# 36V_Supply.net
KiCad netlist of a schematic drawn in Altium Designer
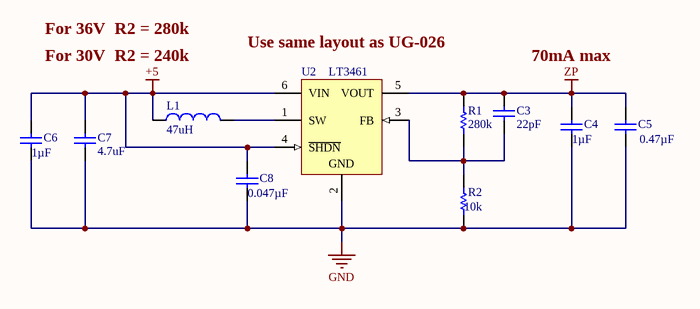
[diagram p0: 36V_Supply.SchDoc]

(export (version "E")
  (design (tool "Eeschema 10.0.6"))
  (components
    (comp (ref "C3")
      (value "22pF")
      (footprint "CAPC1206(3216)170_L")
      (description "CAP CER 22PF 50V C0G/NP0 1206")
      (fields
        (field (name "MANUFACTURER") "KEMET")
        (field (name "MANUFACTURER PART NUMBER") "C1206C220K5GACTU")
      )
      (libsource (lib "Altium Content Vault") (part "CMP-1037-04573-1"))
    )
    (comp (ref "C4")
      (value "CAP CER 1UF 50V X7R 1210")
      (footprint "CAPC1210(3225)100_N")
      (fields
        (field (name "MANUFACTURER") "Taiyo Yuden")
        (field (name "MANUFACTURER PART NUMBER") "UMK325B7105KH-T")
        (field (name "CAPACITANCE") "1µF")
        (field (name "TOLERANCE") "±10%")
      )
      (libsource (lib "Altium Content Vault") (part "CMP-1038-01123-1"))
    )
    (comp (ref "C5")
      (value "CAP CER 0.47UF 50V X7R 1206")
      (footprint "CAPC1206(3216)190_N")
      (fields
        (field (name "MANUFACTURER") "Taiyo Yuden")
        (field (name "MANUFACTURER PART NUMBER") "UMK316B7474KL-T")
        (field (name "CAPACITANCE") "0.47µF")
        (field (name "TOLERANCE") "±10%")
      )
      (libsource (lib "Altium Content Vault") (part "CMP-1037-04570-1"))
    )
    (comp (ref "C6")
      (value "CAP CER 1UF 16V X7R 0805")
      (footprint "CAPC0805(2012)145_N")
      (fields
        (field (name "MANUFACTURER") "Taiyo Yuden")
        (field (name "MANUFACTURER PART NUMBER") "EMK212B7105KG-T")
        (field (name "CAPACITANCE") "1µF")
        (field (name "TOLERANCE") "±10%")
      )
      (libsource (lib "Altium Content Vault") (part "CMP-1036-04795-1"))
    )
    (comp (ref "C7")
      (value "4.7uF")
      (footprint "CAPC0805(2012)145_M")
      (description "CAP CER 4.7UF 16V X7R 0805")
      (fields
        (field (name "MANUFACTURER") "KEMET")
        (field (name "MANUFACTURER PART NUMBER") "C0805C475K4RACTU")
      )
      (libsource (lib "Altium Content Vault") (part "CMP-1036-04750-1"))
    )
    (comp (ref "C8")
      (value "CAP CER 0.047UF 16V X7R 0603")
      (footprint "CAPC0805(2012)145_N")
      (fields
        (field (name "MANUFACTURER") "Murata Electronics North America")
        (field (name "MANUFACTURER PART NUMBER") "GRM188R71C473KA01D")
        (field (name "CAPACITANCE") "0.047µF")
        (field (name "TOLERANCE") "±10%")
      )
      (libsource (lib "Altium Content Vault") (part "CMP-1036-04795-1"))
    )
    (comp (ref "L1")
      (value "47uH")
      (footprint "C1210")
      (description "FIXED IND 47UH 170MA 1.3 OHM SMD")
      (fields
        (field (name "MANUFACTURER") "Murata Electronics North America")
        (field (name "MANUFACTURER PART NUMBER") "LQH32CN470K23L")
      )
      (libsource (lib "Miscellaneous Devices") (part "Inductor"))
    )
    (comp (ref "R1")
      (value "RES SMD 280K OHM 1% 1/8W 0805")
      (footprint "RESC0805(2012)_M")
      (fields
        (field (name "MANUFACTURER") "Vishay Dale")
        (field (name "MANUFACTURER PART NUMBER") "CRCW0805280KFKEA")
        (field (name "RESISTANCE (OHMS)") "280k")
        (field (name "TOLERANCE") "±1%")
      )
      (libsource (lib "Altium Content Vault") (part "CMP-1013-00017-1"))
    )
    (comp (ref "R2")
      (value "RES SMD 10K OHM 1% 1/8W 0805")
      (footprint "RESC0805(2012)_M")
      (fields
        (field (name "MANUFACTURER") "Yageo")
        (field (name "MANUFACTURER PART NUMBER") "RC0805FR-0710KL")
        (field (name "RESISTANCE (OHMS)") "10k")
        (field (name "TOLERANCE") "±1%")
      )
      (libsource (lib "Altium Content Vault") (part "CMP-1013-00017-1"))
    )
    (comp (ref "U2")
      (value "LT3461")
      (footprint "LT-S6-6-TSOT-23_N")
      (description "IC REG BOOST ADJ 0.3A TSOT23-6")
      (libsource (lib "Altium Content Vault") (part "CMP-0491-01698-1"))
    )
  )
  (nets
    (net (code "1") (name "+5") (class "Default")
      (node (ref "C6") (pin "2") (pinfunction "2_2") (pintype "passive"))
      (node (ref "C7") (pin "2") (pinfunction "2_2") (pintype "passive"))
      (node (ref "C8") (pin "2") (pinfunction "2_2") (pintype "passive"))
      (node (ref "L1") (pin "1") (pinfunction "1_1") (pintype "passive"))
      (node (ref "U2") (pin "4") (pinfunction "~{SHDN}_4") (pintype "input"))
      (node (ref "U2") (pin "6") (pinfunction "VIN_6") (pintype "power_in"))
    )
    (net (code "2") (name "GND") (class "Default")
      (node (ref "C4") (pin "1") (pinfunction "1_1") (pintype "passive"))
      (node (ref "C5") (pin "1") (pinfunction "1_1") (pintype "passive"))
      (node (ref "C6") (pin "1") (pinfunction "1_1") (pintype "passive"))
      (node (ref "C7") (pin "1") (pinfunction "1_1") (pintype "passive"))
      (node (ref "C8") (pin "1") (pinfunction "1_1") (pintype "passive"))
      (node (ref "R2") (pin "2") (pinfunction "2_2") (pintype "passive"))
      (node (ref "U2") (pin "2") (pinfunction "GND_2") (pintype "power_in"))
    )
    (net (code "3") (name "Net-(U2-FB)") (class "Default")
      (node (ref "C3") (pin "1") (pinfunction "1_1") (pintype "passive"))
      (node (ref "R1") (pin "2") (pinfunction "2_2") (pintype "passive"))
      (node (ref "R2") (pin "1") (pinfunction "1_1") (pintype "passive"))
      (node (ref "U2") (pin "3") (pinfunction "FB_3") (pintype "input"))
    )
    (net (code "4") (name "Net-(U2-SW)") (class "Default")
      (node (ref "L1") (pin "2") (pinfunction "2_2") (pintype "passive"))
      (node (ref "U2") (pin "1") (pinfunction "SW_1") (pintype "passive"))
    )
    (net (code "5") (name "ZP") (class "Default")
      (node (ref "C3") (pin "2") (pinfunction "2_2") (pintype "passive"))
      (node (ref "C4") (pin "2") (pinfunction "2_2") (pintype "passive"))
      (node (ref "C5") (pin "2") (pinfunction "2_2") (pintype "passive"))
      (node (ref "R1") (pin "1") (pinfunction "1_1") (pintype "passive"))
      (node (ref "U2") (pin "5") (pinfunction "VOUT_5") (pintype "power_in"))
    )
  )
)
